# RS485.net
KiCad netlist of a schematic drawn in Altium Designer
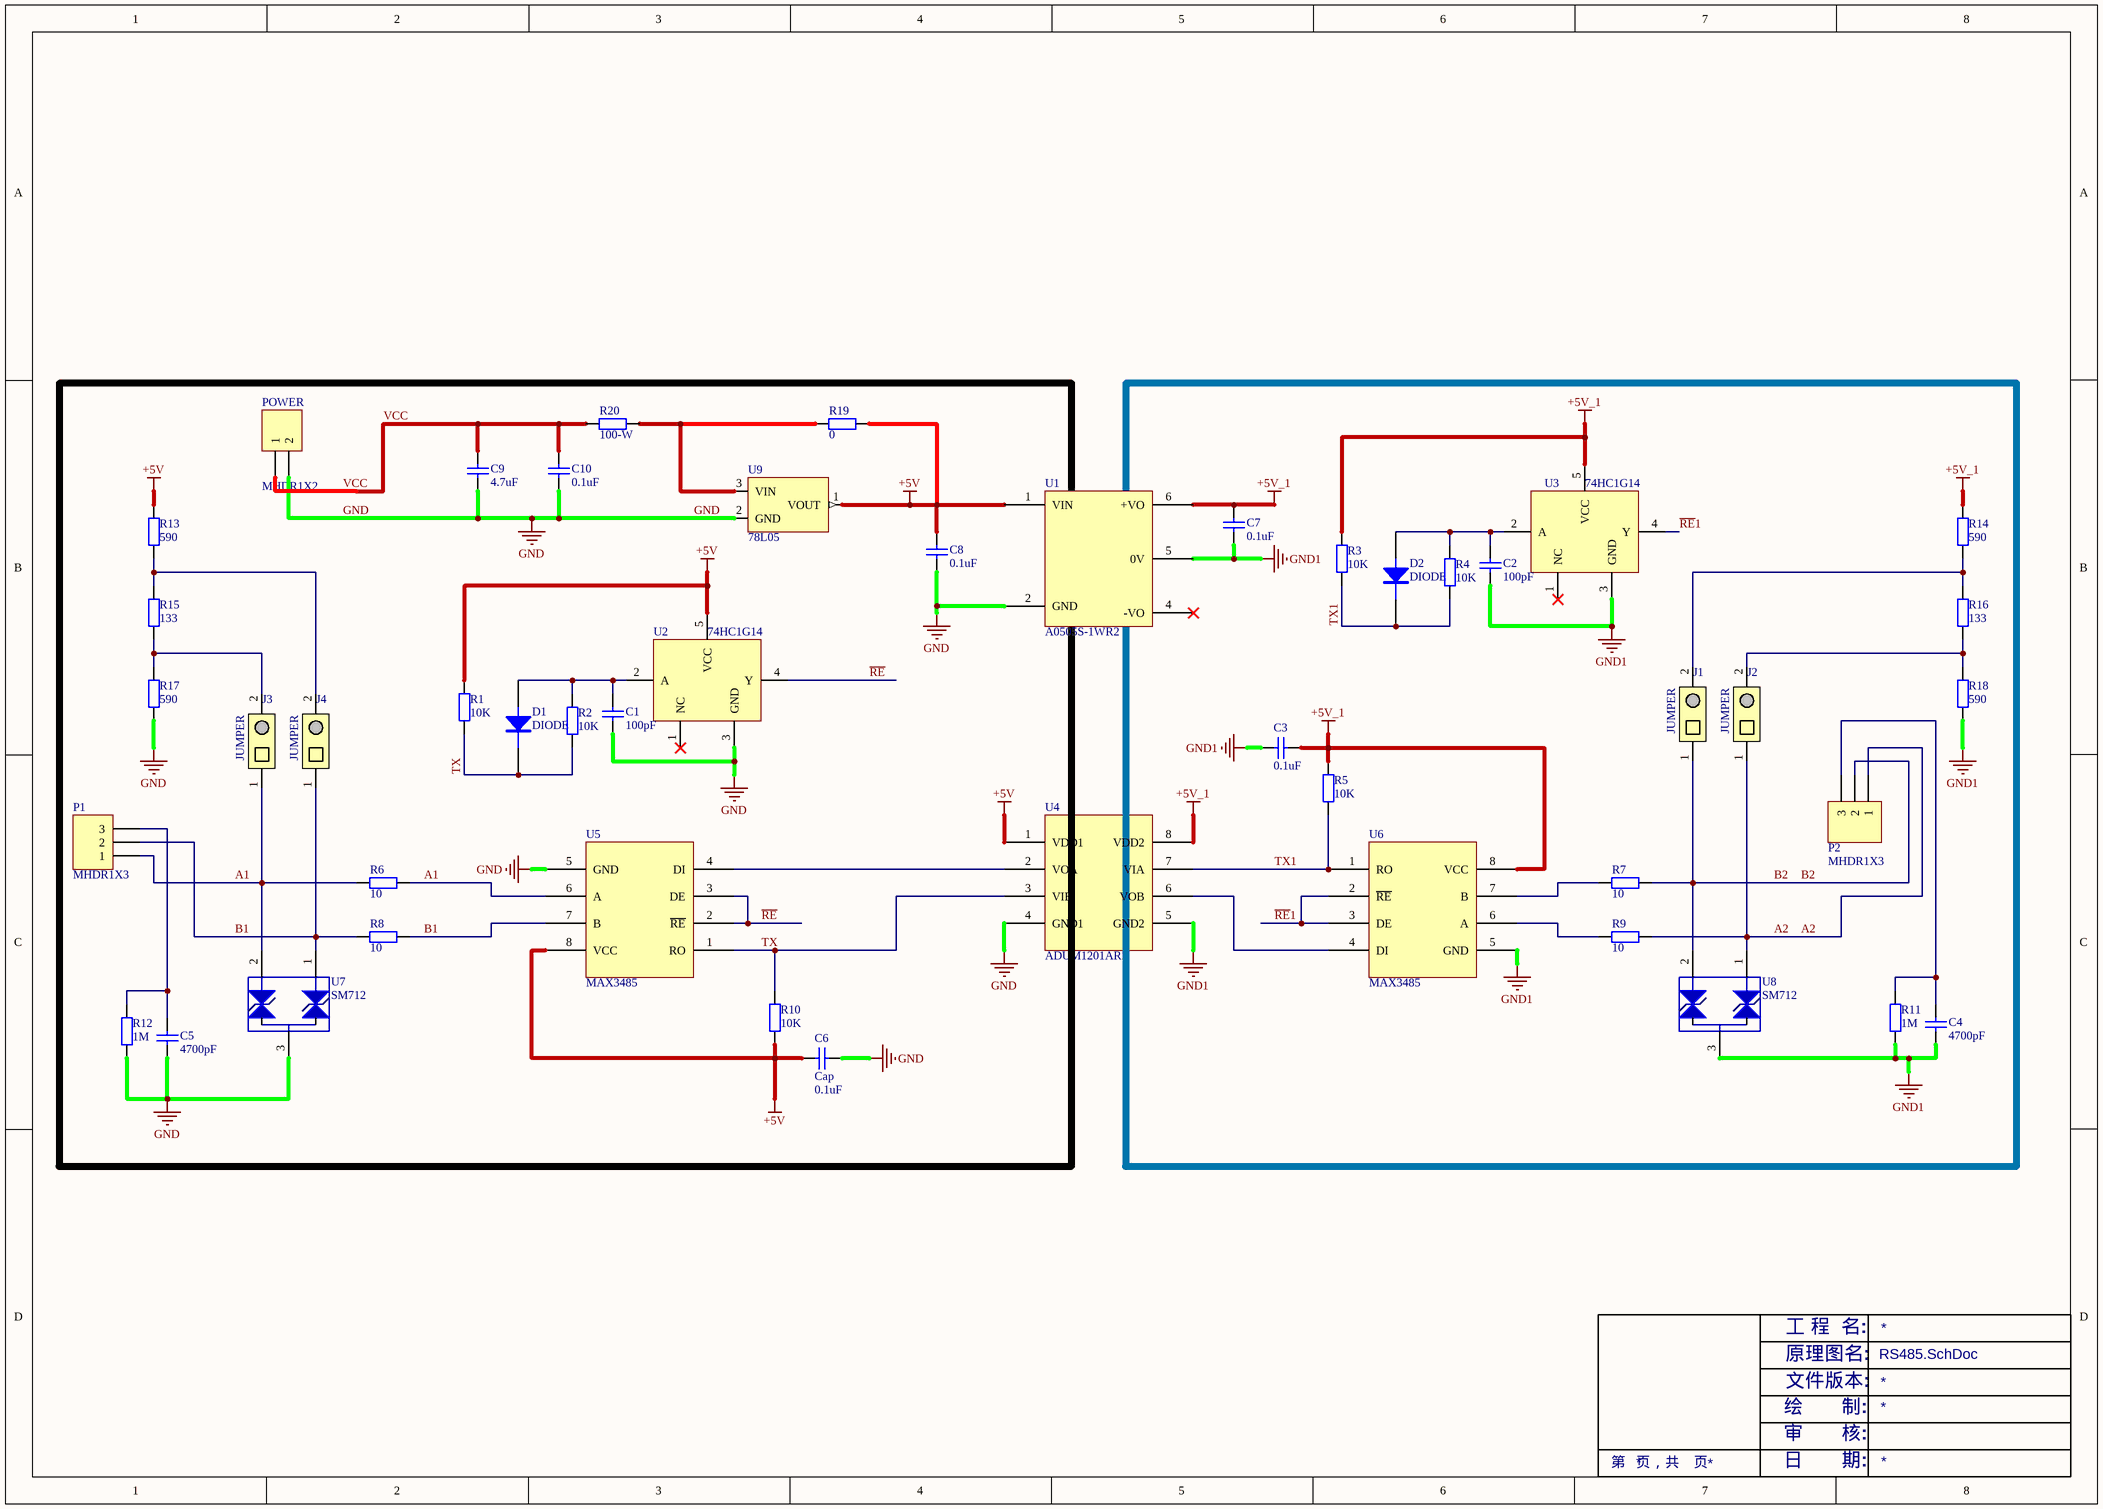
[diagram p0: RS485.SchDoc]

(export (version "E")
  (design (tool "Eeschema 10.0.6"))
  (components
    (comp (ref "C1")
      (value "100pF")
      (footprint "CC0603")
      (description "Capacitor")
      (fields (field (name "PUBLISHER") "Altium Limited"))
      (libsource (lib "Miscellaneous Devices") (part "Cap"))
    )
    (comp (ref "C2")
      (value "100pF")
      (footprint "CC0603")
      (description "Capacitor")
      (fields (field (name "PUBLISHER") "Altium Limited"))
      (libsource (lib "Miscellaneous Devices") (part "Cap"))
    )
    (comp (ref "C3")
      (value "0.1uF")
      (footprint "CC0603")
      (description "Capacitor")
      (fields (field (name "PUBLISHER") "Altium Limited"))
      (libsource (lib "Miscellaneous Devices") (part "Cap"))
    )
    (comp (ref "C4")
      (value "4700pF")
      (footprint "CC0603")
      (description "Capacitor")
      (fields (field (name "PUBLISHER") "Altium Limited"))
      (libsource (lib "Miscellaneous Devices") (part "Cap"))
    )
    (comp (ref "C5")
      (value "4700pF")
      (footprint "CC0603")
      (description "Capacitor")
      (fields (field (name "PUBLISHER") "Altium Limited"))
      (libsource (lib "Miscellaneous Devices") (part "Cap"))
    )
    (comp (ref "C6")
      (value "Cap")
      (footprint "CC0603")
      (description "Capacitor")
      (fields (field (name "ALTIUM_VALUE") "0.1uF") (field (name "PUBLISHER") "Altium Limited"))
      (libsource (lib "Miscellaneous Devices") (part "Cap"))
    )
    (comp (ref "C7")
      (value "0.1uF")
      (footprint "CC0603")
      (description "Capacitor")
      (fields (field (name "PUBLISHER") "Altium Limited"))
      (libsource (lib "Miscellaneous Devices") (part "Cap"))
    )
    (comp (ref "C8")
      (value "0.1uF")
      (footprint "CC0603")
      (description "Capacitor")
      (fields (field (name "PUBLISHER") "Altium Limited"))
      (libsource (lib "Miscellaneous Devices") (part "Cap"))
    )
    (comp (ref "C9")
      (value "4.7uF")
      (footprint "CC0603")
      (description "Capacitor")
      (fields (field (name "PUBLISHER") "Altium Limited"))
      (libsource (lib "Miscellaneous Devices") (part "Cap"))
    )
    (comp (ref "C10")
      (value "0.1uF")
      (footprint "CC0603")
      (description "Capacitor")
      (fields (field (name "PUBLISHER") "Altium Limited"))
      (libsource (lib "Miscellaneous Devices") (part "Cap"))
    )
    (comp (ref "D1") (value "DIODE") (footprint "SOD323") (libsource (lib "woylib2015") (part "DIODE")))
    (comp (ref "D2") (value "DIODE") (footprint "SOD323") (libsource (lib "woylib2015") (part "DIODE")))
    (comp (ref "J1") (value "JUMPER") (footprint "SIP2-2.54MM") (libsource (lib "Connector") (part "JUMPER")))
    (comp (ref "J2") (value "JUMPER") (footprint "SIP2-2.54MM") (libsource (lib "Connector") (part "JUMPER")))
    (comp (ref "J3") (value "JUMPER") (footprint "SIP2-2.54MM") (libsource (lib "Connector") (part "JUMPER")))
    (comp (ref "J4") (value "JUMPER") (footprint "SIP2-2.54MM") (libsource (lib "Connector") (part "JUMPER")))
    (comp (ref "P1")
      (value "MHDR1X3")
      (footprint "HEADER_35MM")
      (description "Header, 3-Pin")
      (fields (field (name "PUBLISHER") "Altium Limited"))
      (libsource (lib "Miscellaneous Connectors") (part "MHDR1X3"))
    )
    (comp (ref "P2")
      (value "MHDR1X3")
      (footprint "HEADER_35MM")
      (description "Header, 3-Pin")
      (fields (field (name "PUBLISHER") "Altium Limited"))
      (libsource (lib "") (part "MHDR1X3_1"))
    )
    (comp (ref "POWER")
      (value "MHDR1X2")
      (footprint "HEADER_35MM_2")
      (description "Header, 2-Pin")
      (fields (field (name "PUBLISHER") "Altium Limited"))
      (libsource (lib "Miscellaneous Connectors") (part "MHDR1X2"))
    )
    (comp (ref "R1")
      (value "10K")
      (footprint "CC0603")
      (description "Resistor")
      (fields (field (name "PUBLISHER") "Altium Limited"))
      (libsource (lib "") (part "Res2_1"))
    )
    (comp (ref "R2")
      (value "10K")
      (footprint "CC0603")
      (description "Resistor")
      (fields (field (name "PUBLISHER") "Altium Limited"))
      (libsource (lib "") (part "Res2_1"))
    )
    (comp (ref "R3")
      (value "10K")
      (footprint "CC0603")
      (description "Resistor")
      (fields (field (name "PUBLISHER") "Altium Limited"))
      (libsource (lib "") (part "Res2_1"))
    )
    (comp (ref "R4")
      (value "10K")
      (footprint "CC0603")
      (description "Resistor")
      (fields (field (name "PUBLISHER") "Altium Limited"))
      (libsource (lib "") (part "Res2_1"))
    )
    (comp (ref "R5")
      (value "10K")
      (footprint "CC0603")
      (description "Resistor")
      (fields (field (name "PUBLISHER") "Altium Limited"))
      (libsource (lib "") (part "Res2_1"))
    )
    (comp (ref "R6")
      (value "10")
      (footprint "CC0603")
      (description "Resistor")
      (fields (field (name "PUBLISHER") "Altium Limited"))
      (libsource (lib "Miscellaneous Devices") (part "Res2"))
    )
    (comp (ref "R7")
      (value "10")
      (footprint "CC0603")
      (description "Resistor")
      (fields (field (name "PUBLISHER") "Altium Limited"))
      (libsource (lib "") (part "Res2_2"))
    )
    (comp (ref "R8")
      (value "10")
      (footprint "CC0603")
      (description "Resistor")
      (fields (field (name "PUBLISHER") "Altium Limited"))
      (libsource (lib "Miscellaneous Devices") (part "Res2"))
    )
    (comp (ref "R9")
      (value "10")
      (footprint "CC0603")
      (description "Resistor")
      (fields (field (name "PUBLISHER") "Altium Limited"))
      (libsource (lib "") (part "Res2_2"))
    )
    (comp (ref "R10")
      (value "10K")
      (footprint "CC0603")
      (description "Resistor")
      (fields (field (name "PUBLISHER") "Altium Limited"))
      (libsource (lib "") (part "Res2_3"))
    )
    (comp (ref "R11")
      (value "1M")
      (footprint "CC0603")
      (description "Resistor")
      (fields (field (name "PUBLISHER") "Altium Limited"))
      (libsource (lib "") (part "Res2_3"))
    )
    (comp (ref "R12")
      (value "1M")
      (footprint "CC0603")
      (description "Resistor")
      (fields (field (name "PUBLISHER") "Altium Limited"))
      (libsource (lib "") (part "Res2_3"))
    )
    (comp (ref "R13")
      (value "590")
      (footprint "CC0603")
      (description "Resistor")
      (fields (field (name "PUBLISHER") "Altium Limited"))
      (libsource (lib "") (part "Res2_1"))
    )
    (comp (ref "R14")
      (value "590")
      (footprint "CC0603")
      (description "Resistor")
      (fields (field (name "PUBLISHER") "Altium Limited"))
      (libsource (lib "") (part "Res2_1"))
    )
    (comp (ref "R15")
      (value "133")
      (footprint "CC0603")
      (description "Resistor")
      (fields (field (name "PUBLISHER") "Altium Limited"))
      (libsource (lib "") (part "Res2_1"))
    )
    (comp (ref "R16")
      (value "133")
      (footprint "CC0603")
      (description "Resistor")
      (fields (field (name "PUBLISHER") "Altium Limited"))
      (libsource (lib "") (part "Res2_1"))
    )
    (comp (ref "R17")
      (value "590")
      (footprint "CC0603")
      (description "Resistor")
      (fields (field (name "PUBLISHER") "Altium Limited"))
      (libsource (lib "") (part "Res2_1"))
    )
    (comp (ref "R18")
      (value "590")
      (footprint "CC0603")
      (description "Resistor")
      (fields (field (name "PUBLISHER") "Altium Limited"))
      (libsource (lib "") (part "Res2_1"))
    )
    (comp (ref "R19")
      (value "0")
      (footprint "CC0603")
      (description "Resistor")
      (fields (field (name "PUBLISHER") "Altium Limited"))
      (libsource (lib "") (part "Res2_2"))
    )
    (comp (ref "R20")
      (value "100-W")
      (footprint "AXIAL-0.3")
      (description "Resistor")
      (fields (field (name "PUBLISHER") "Altium Limited"))
      (libsource (lib "") (part "Res2_2"))
    )
    (comp (ref "U1")
      (value "A0505S-1WR2")
      (footprint "A0505S-1W-2R")
      (libsource (lib "IC") (part "A0505S-1WR2"))
    )
    (comp (ref "U2")
      (value "74HC1G14")
      (footprint "SOT-23-5")
      (libsource (lib "woylib2015") (part "74HC1G14"))
    )
    (comp (ref "U3")
      (value "74HC1G14")
      (footprint "SOT-23-5")
      (libsource (lib "woylib2015") (part "74HC1G14"))
    )
    (comp (ref "U4")
      (value "ADUM1201ARZ")
      (footprint "SO-8")
      (libsource (lib "woylib2015") (part "ADUM1201ARZ"))
    )
    (comp (ref "U5") (value "MAX3485") (footprint "SO-8") (libsource (lib "woylib2015") (part "MAX3485")))
    (comp (ref "U6") (value "MAX3485") (footprint "SO-8") (libsource (lib "") (part "MAX3485_1")))
    (comp (ref "U7") (value "SM712") (footprint "SOT-23W") (libsource (lib "woylib2015") (part "SM712")))
    (comp (ref "U8") (value "SM712") (footprint "SOT-23W") (libsource (lib "woylib2015") (part "SM712")))
    (comp (ref "U9")
      (value "78L05")
      (footprint "TO-92")
      (description "CI-78L05")
      (libsource (lib "woylib2015") (part "78L05"))
    )
  )
  (nets
    (net (code "1") (name "+5V") (class "Default")
      (node (ref "C6") (pin "1") (pinfunction "1_1") (pintype "passive"))
      (node (ref "C8") (pin "1") (pinfunction "1_1") (pintype "passive"))
      (node (ref "R1") (pin "2") (pinfunction "2_2") (pintype "passive"))
      (node (ref "R10") (pin "2") (pinfunction "2_2") (pintype "passive"))
      (node (ref "R13") (pin "2") (pinfunction "2_2") (pintype "passive"))
      (node (ref "R19") (pin "1") (pinfunction "1_1") (pintype "passive"))
      (node (ref "U1") (pin "1") (pinfunction "VIN_1") (pintype "passive"))
      (node (ref "U2") (pin "5") (pinfunction "VCC_5") (pintype "passive"))
      (node (ref "U4") (pin "1") (pinfunction "VDD1_1") (pintype "passive"))
      (node (ref "U5") (pin "8") (pinfunction "VCC_8") (pintype "passive"))
      (node (ref "U9") (pin "1") (pinfunction "VOUT_1") (pintype "output"))
    )
    (net (code "2") (name "+5V_1") (class "Default")
      (node (ref "C3") (pin "1") (pinfunction "1_1") (pintype "passive"))
      (node (ref "C7") (pin "1") (pinfunction "1_1") (pintype "passive"))
      (node (ref "R14") (pin "2") (pinfunction "2_2") (pintype "passive"))
      (node (ref "R3") (pin "2") (pinfunction "2_2") (pintype "passive"))
      (node (ref "R5") (pin "2") (pinfunction "2_2") (pintype "passive"))
      (node (ref "U1") (pin "6") (pinfunction "+VO_6") (pintype "passive"))
      (node (ref "U3") (pin "5") (pinfunction "VCC_5") (pintype "passive"))
      (node (ref "U4") (pin "8") (pinfunction "VDD2_8") (pintype "passive"))
      (node (ref "U6") (pin "8") (pinfunction "VCC_8") (pintype "passive"))
    )
    (net (code "3") (name "/A1") (class "Default")
      (node (ref "J3") (pin "1") (pinfunction "1_1") (pintype "passive"))
      (node (ref "P1") (pin "1") (pinfunction "1_1") (pintype "passive"))
      (node (ref "R6") (pin "1") (pinfunction "1_1") (pintype "passive"))
      (node (ref "R6") (pin "2") (pinfunction "2_2") (pintype "passive"))
      (node (ref "U5") (pin "6") (pinfunction "A_6") (pintype "passive"))
      (node (ref "U7") (pin "2") (pinfunction "2_2") (pintype "passive"))
    )
    (net (code "4") (name "/A2") (class "Default")
      (node (ref "J2") (pin "1") (pinfunction "1_1") (pintype "passive"))
      (node (ref "P2") (pin "1") (pinfunction "1_1") (pintype "passive"))
      (node (ref "R9") (pin "1") (pinfunction "1_1") (pintype "passive"))
      (node (ref "U8") (pin "1") (pinfunction "1_1") (pintype "passive"))
    )
    (net (code "5") (name "/B1") (class "Default")
      (node (ref "J4") (pin "1") (pinfunction "1_1") (pintype "passive"))
      (node (ref "P1") (pin "2") (pinfunction "2_2") (pintype "passive"))
      (node (ref "R8") (pin "1") (pinfunction "1_1") (pintype "passive"))
      (node (ref "R8") (pin "2") (pinfunction "2_2") (pintype "passive"))
      (node (ref "U5") (pin "7") (pinfunction "B_7") (pintype "passive"))
      (node (ref "U7") (pin "1") (pinfunction "1_1") (pintype "passive"))
    )
    (net (code "6") (name "/B2") (class "Default")
      (node (ref "J1") (pin "1") (pinfunction "1_1") (pintype "passive"))
      (node (ref "P2") (pin "2") (pinfunction "2_2") (pintype "passive"))
      (node (ref "R7") (pin "1") (pinfunction "1_1") (pintype "passive"))
      (node (ref "U8") (pin "2") (pinfunction "2_2") (pintype "passive"))
    )
    (net (code "7") (name "/TX") (class "Default")
      (node (ref "D1") (pin "2") (pinfunction "K_2") (pintype "passive"))
      (node (ref "R1") (pin "1") (pinfunction "1_1") (pintype "passive"))
      (node (ref "R10") (pin "1") (pinfunction "1_1") (pintype "passive"))
      (node (ref "R2") (pin "1") (pinfunction "1_1") (pintype "passive"))
      (node (ref "U4") (pin "3") (pinfunction "VIB_3") (pintype "passive"))
      (node (ref "U5") (pin "1") (pinfunction "RO_1") (pintype "passive"))
    )
    (net (code "8") (name "/TX1") (class "Default")
      (node (ref "D2") (pin "2") (pinfunction "K_2") (pintype "passive"))
      (node (ref "R3") (pin "1") (pinfunction "1_1") (pintype "passive"))
      (node (ref "R4") (pin "1") (pinfunction "1_1") (pintype "passive"))
      (node (ref "R5") (pin "1") (pinfunction "1_1") (pintype "passive"))
      (node (ref "U4") (pin "7") (pinfunction "VIA_7") (pintype "passive"))
      (node (ref "U6") (pin "1") (pinfunction "RO_1") (pintype "passive"))
    )
    (net (code "9") (name "/VCC") (class "Default")
      (node (ref "C10") (pin "1") (pinfunction "1_1") (pintype "passive"))
      (node (ref "C9") (pin "1") (pinfunction "1_1") (pintype "passive"))
      (node (ref "POWER") (pin "1") (pinfunction "1_1") (pintype "passive"))
      (node (ref "R20") (pin "2") (pinfunction "2_2") (pintype "passive"))
    )
    (net (code "10") (name "/~{RE}") (class "Default")
      (node (ref "U2") (pin "4") (pinfunction "Y_4") (pintype "passive"))
      (node (ref "U5") (pin "2") (pinfunction "~{RE}_2") (pintype "passive"))
      (node (ref "U5") (pin "3") (pinfunction "DE_3") (pintype "passive"))
    )
    (net (code "11") (name "/~{RE}1") (class "Default")
      (node (ref "U3") (pin "4") (pinfunction "Y_4") (pintype "passive"))
      (node (ref "U6") (pin "2") (pinfunction "~{RE}_2") (pintype "passive"))
      (node (ref "U6") (pin "3") (pinfunction "DE_3") (pintype "passive"))
    )
    (net (code "12") (name "GND") (class "Default")
      (node (ref "C1") (pin "1") (pinfunction "1_1") (pintype "passive"))
      (node (ref "C10") (pin "2") (pinfunction "2_2") (pintype "passive"))
      (node (ref "C5") (pin "1") (pinfunction "1_1") (pintype "passive"))
      (node (ref "C6") (pin "2") (pinfunction "2_2") (pintype "passive"))
      (node (ref "C8") (pin "2") (pinfunction "2_2") (pintype "passive"))
      (node (ref "C9") (pin "2") (pinfunction "2_2") (pintype "passive"))
      (node (ref "POWER") (pin "2") (pinfunction "2_2") (pintype "passive"))
      (node (ref "R12") (pin "2") (pinfunction "2_2") (pintype "passive"))
      (node (ref "R17") (pin "1") (pinfunction "1_1") (pintype "passive"))
      (node (ref "U1") (pin "2") (pinfunction "GND_2") (pintype "passive"))
      (node (ref "U2") (pin "3") (pinfunction "GND_3") (pintype "passive"))
      (node (ref "U4") (pin "4") (pinfunction "GND1_4") (pintype "passive"))
      (node (ref "U5") (pin "5") (pinfunction "GND_5") (pintype "passive"))
      (node (ref "U7") (pin "3") (pinfunction "3_3") (pintype "passive"))
      (node (ref "U9") (pin "2") (pinfunction "GND_2") (pintype "power_in"))
    )
    (net (code "13") (name "GND1") (class "Default")
      (node (ref "C2") (pin "1") (pinfunction "1_1") (pintype "passive"))
      (node (ref "C3") (pin "2") (pinfunction "2_2") (pintype "passive"))
      (node (ref "C4") (pin "1") (pinfunction "1_1") (pintype "passive"))
      (node (ref "C7") (pin "2") (pinfunction "2_2") (pintype "passive"))
      (node (ref "R11") (pin "2") (pinfunction "2_2") (pintype "passive"))
      (node (ref "R18") (pin "1") (pinfunction "1_1") (pintype "passive"))
      (node (ref "U1") (pin "5") (pinfunction "0V_5") (pintype "passive"))
      (node (ref "U3") (pin "3") (pinfunction "GND_3") (pintype "passive"))
      (node (ref "U4") (pin "5") (pinfunction "GND2_5") (pintype "passive"))
      (node (ref "U6") (pin "5") (pinfunction "GND_5") (pintype "passive"))
      (node (ref "U8") (pin "3") (pinfunction "3_3") (pintype "passive"))
    )
    (net (code "14") (name "Net-(C4-Pad2)") (class "Default")
      (node (ref "C4") (pin "2") (pinfunction "2_2") (pintype "passive"))
      (node (ref "P2") (pin "3") (pinfunction "3_3") (pintype "passive"))
      (node (ref "R11") (pin "1") (pinfunction "1_1") (pintype "passive"))
    )
    (net (code "15") (name "Net-(C5-Pad2)") (class "Default")
      (node (ref "C5") (pin "2") (pinfunction "2_2") (pintype "passive"))
      (node (ref "P1") (pin "3") (pinfunction "3_3") (pintype "passive"))
      (node (ref "R12") (pin "1") (pinfunction "1_1") (pintype "passive"))
    )
    (net (code "16") (name "Net-(D1-A)") (class "Default")
      (node (ref "C1") (pin "2") (pinfunction "2_2") (pintype "passive"))
      (node (ref "D1") (pin "1") (pinfunction "A_1") (pintype "passive"))
      (node (ref "R2") (pin "2") (pinfunction "2_2") (pintype "passive"))
      (node (ref "U2") (pin "2") (pinfunction "A_2") (pintype "passive"))
    )
    (net (code "17") (name "Net-(D2-A)") (class "Default")
      (node (ref "C2") (pin "2") (pinfunction "2_2") (pintype "passive"))
      (node (ref "D2") (pin "1") (pinfunction "A_1") (pintype "passive"))
      (node (ref "R4") (pin "2") (pinfunction "2_2") (pintype "passive"))
      (node (ref "U3") (pin "2") (pinfunction "A_2") (pintype "passive"))
    )
    (net (code "18") (name "Net-(J1-Pad2)") (class "Default")
      (node (ref "J1") (pin "2") (pinfunction "2_2") (pintype "passive"))
      (node (ref "R14") (pin "1") (pinfunction "1_1") (pintype "passive"))
      (node (ref "R16") (pin "2") (pinfunction "2_2") (pintype "passive"))
    )
    (net (code "19") (name "Net-(J2-Pad2)") (class "Default")
      (node (ref "J2") (pin "2") (pinfunction "2_2") (pintype "passive"))
      (node (ref "R16") (pin "1") (pinfunction "1_1") (pintype "passive"))
      (node (ref "R18") (pin "2") (pinfunction "2_2") (pintype "passive"))
    )
    (net (code "20") (name "Net-(J3-Pad2)") (class "Default")
      (node (ref "J3") (pin "2") (pinfunction "2_2") (pintype "passive"))
      (node (ref "R15") (pin "1") (pinfunction "1_1") (pintype "passive"))
      (node (ref "R17") (pin "2") (pinfunction "2_2") (pintype "passive"))
    )
    (net (code "21") (name "Net-(J4-Pad2)") (class "Default")
      (node (ref "J4") (pin "2") (pinfunction "2_2") (pintype "passive"))
      (node (ref "R13") (pin "1") (pinfunction "1_1") (pintype "passive"))
      (node (ref "R15") (pin "2") (pinfunction "2_2") (pintype "passive"))
    )
    (net (code "22") (name "Net-(U4-VOA)") (class "Default")
      (node (ref "U4") (pin "2") (pinfunction "VOA_2") (pintype "passive"))
      (node (ref "U5") (pin "4") (pinfunction "DI_4") (pintype "passive"))
    )
    (net (code "23") (name "Net-(U4-VOB)") (class "Default")
      (node (ref "U4") (pin "6") (pinfunction "VOB_6") (pintype "passive"))
      (node (ref "U6") (pin "4") (pinfunction "DI_4") (pintype "passive"))
    )
    (net (code "24") (name "Net-(U6-A)") (class "Default")
      (node (ref "R9") (pin "2") (pinfunction "2_2") (pintype "passive"))
      (node (ref "U6") (pin "6") (pinfunction "A_6") (pintype "passive"))
    )
    (net (code "25") (name "Net-(U6-B)") (class "Default")
      (node (ref "R7") (pin "2") (pinfunction "2_2") (pintype "passive"))
      (node (ref "U6") (pin "7") (pinfunction "B_7") (pintype "passive"))
    )
    (net (code "26") (name "Net-(U9-VIN)") (class "Default")
      (node (ref "R19") (pin "2") (pinfunction "2_2") (pintype "passive"))
      (node (ref "R20") (pin "1") (pinfunction "1_1") (pintype "passive"))
      (node (ref "U9") (pin "3") (pinfunction "VIN_3") (pintype "power_in"))
    )
    (net (code "27") (name "unconnected-(U1--VO-Pad4)") (class "Default")
      (node (ref "U1") (pin "4") (pinfunction "-VO_4") (pintype "passive+no_connect"))
    )
    (net (code "28") (name "unconnected-(U2-NC-Pad1)") (class "Default")
      (node (ref "U2") (pin "1") (pinfunction "NC_1") (pintype "passive+no_connect"))
    )
    (net (code "29") (name "unconnected-(U3-NC-Pad1)") (class "Default")
      (node (ref "U3") (pin "1") (pinfunction "NC_1") (pintype "passive+no_connect"))
    )
  )
)
